# design.net
KiCad netlist of a schematic drawn in Altium Designer
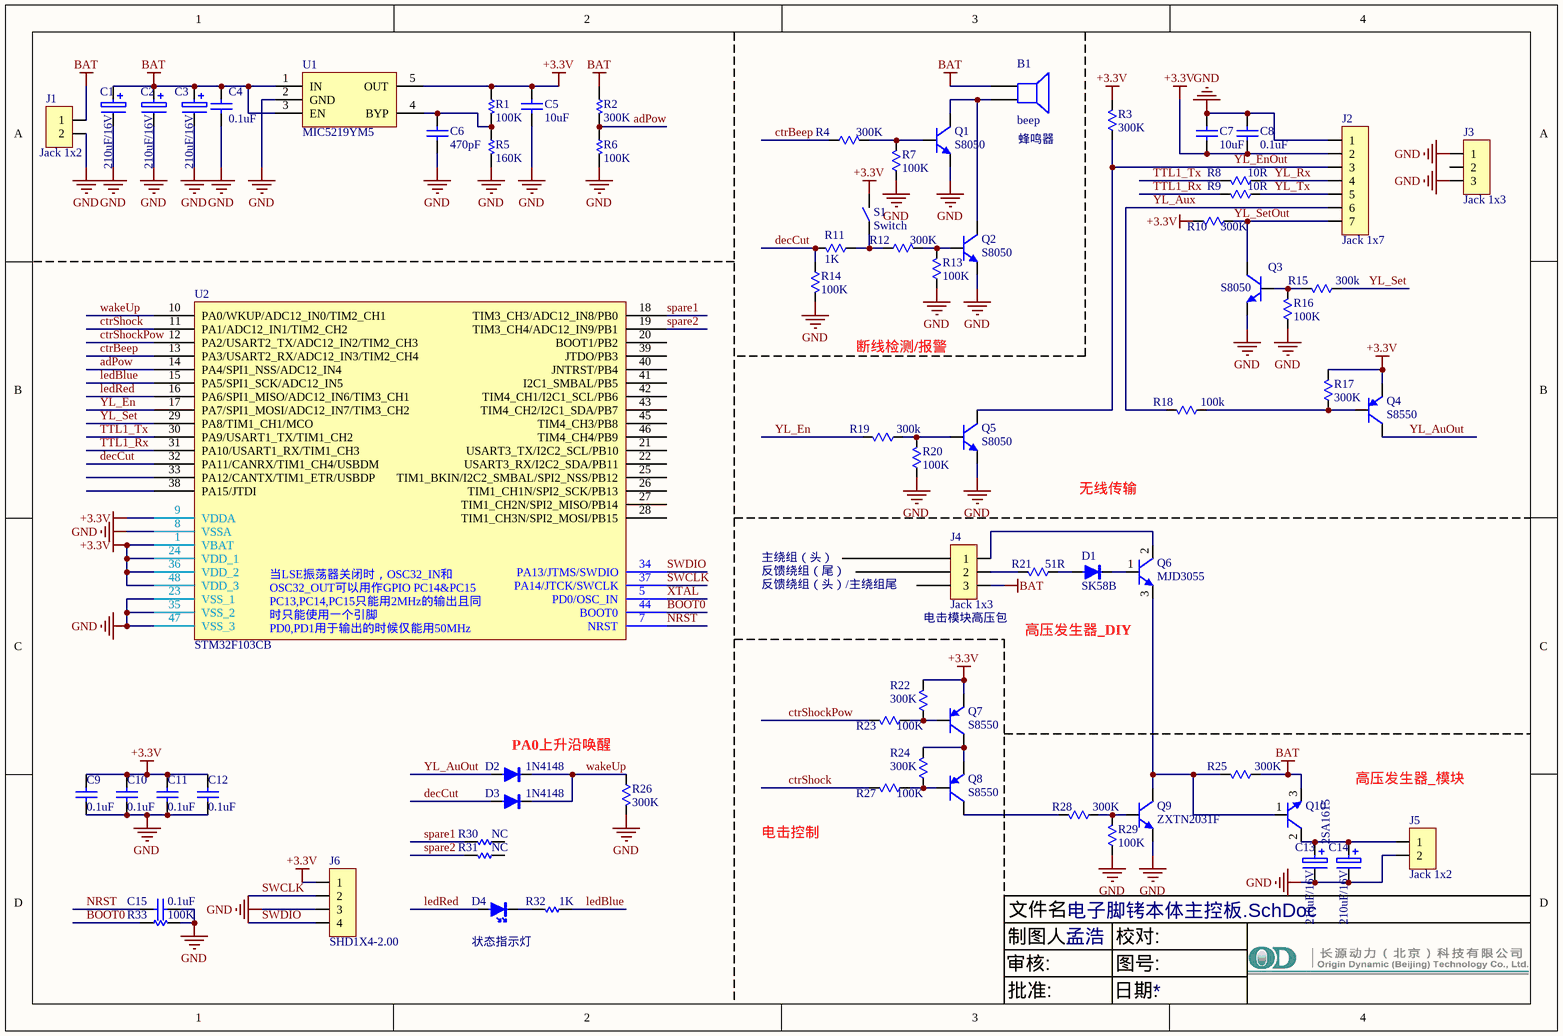
[diagram p0: 电子脚铐本体主控板.SchDoc]

(export (version "E")
  (design (tool "Eeschema 10.0.6"))
  (components
    (comp (ref "B1")
      (value "beep")
      (footprint "Jk1*2-2.0")
      (description "Loudspeaker")
      (fields (field (name "PUBLISHER") "Altium Limited"))
      (libsource (lib "Miscellaneous Devices") (part "Speaker"))
    )
    (comp (ref "C1") (value "210uF/16V") (footprint "C7343") (libsource (lib "RLCYDF") (part "Cap Poll")))
    (comp (ref "C2") (value "210uF/16V") (footprint "C7343") (libsource (lib "RLCYDF") (part "Cap Poll")))
    (comp (ref "C3") (value "210uF/16V") (footprint "C7343") (libsource (lib "RLCYDF") (part "Cap Poll")))
    (comp (ref "C4") (value "0.1uF") (footprint "C0603") (libsource (lib "RLCYDF") (part "Cap Semi")))
    (comp (ref "C5")
      (value "10uF")
      (footprint "C0603")
      (description "CAP")
      (fields (field (name "PUBLISHER") "Altium Limited"))
      (libsource (lib "Passive Components Class") (part "CAP"))
    )
    (comp (ref "C6")
      (value "470pF")
      (footprint "C0603")
      (description "CAP")
      (fields (field (name "PUBLISHER") "Altium Limited"))
      (libsource (lib "Passive Components Class") (part "CAP"))
    )
    (comp (ref "C7")
      (value "10uF")
      (footprint "C0603")
      (description "CAP")
      (fields (field (name "PUBLISHER") "Altium Limited"))
      (libsource (lib "Passive Components Class") (part "CAP"))
    )
    (comp (ref "C8")
      (value "0.1uF")
      (footprint "C0603")
      (description "CAP")
      (fields (field (name "PUBLISHER") "Altium Limited"))
      (libsource (lib "Passive Components Class") (part "CAP"))
    )
    (comp (ref "C9") (value "0.1uF") (footprint "C0603") (libsource (lib "RLCYDF") (part "Cap Semi")))
    (comp (ref "C10") (value "0.1uF") (footprint "C0603") (libsource (lib "RLCYDF") (part "Cap Semi")))
    (comp (ref "C11") (value "0.1uF") (footprint "C0603") (libsource (lib "RLCYDF") (part "Cap Semi")))
    (comp (ref "C12") (value "0.1uF") (footprint "C0603") (libsource (lib "RLCYDF") (part "Cap Semi")))
    (comp (ref "C13") (value "210uF/16V") (footprint "C7343") (libsource (lib "RLCYDF") (part "Cap Poll")))
    (comp (ref "C14") (value "210uF/16V") (footprint "C7343") (libsource (lib "RLCYDF") (part "Cap Poll")))
    (comp (ref "C15") (value "0.1uF") (footprint "C0603") (libsource (lib "RLCYDF") (part "Cap Semi")))
    (comp (ref "D1")
      (value "SK58B")
      (footprint "SMB")
      (description "Silicon Epitaxial Planar Diodes")
      (libsource (lib "Passive Components Class") (part "DIODE-SWITCHING"))
    )
    (comp (ref "D2")
      (value "1N4148")
      (footprint "SOD-80-S")
      (description "Silicon Epitaxial Planar Diodes")
      (libsource (lib "Passive Components Class") (part "DIODE-SWITCHING"))
    )
    (comp (ref "D3")
      (value "1N4148")
      (footprint "SOD-80-S")
      (description "Silicon Epitaxial Planar Diodes")
      (libsource (lib "Passive Components Class") (part "DIODE-SWITCHING"))
    )
    (comp (ref "D4")
      (value "LED")
      (footprint "Jk1*2-2.0")
      (libsource (lib "Passive Components Class") (part "LED"))
    )
    (comp (ref "J1")
      (value "Jack 1x2")
      (footprint "HDR1X2")
      (description "插座")
      (libsource (lib "Connector") (part "Jack 1x2"))
    )
    (comp (ref "J2")
      (value "Jack 1x7")
      (footprint "Jk1*7-2.0")
      (description "插座")
      (libsource (lib "Connector") (part "Jack 1x7"))
    )
    (comp (ref "J3")
      (value "Jack 1x3")
      (footprint "Jk1*3-2.0")
      (description "插座")
      (libsource (lib "Connector") (part "Jack 1x3"))
    )
    (comp (ref "J4")
      (value "Jack 1x3")
      (footprint "Jk1*3-2.0")
      (description "插座")
      (libsource (lib "") (part "Jack 1x3_1"))
    )
    (comp (ref "J5")
      (value "Jack 1x2")
      (footprint "Jk1*2-2.0")
      (description "插座")
      (libsource (lib "") (part "Jack 1x2_1"))
    )
    (comp (ref "J6")
      (value "SHD1X4-2.00")
      (footprint "Jk1*4-2.0")
      (libsource (lib "Connector Class") (part "HEADER1X4"))
    )
    (comp (ref "Q1")
      (value "S8050")
      (footprint "SOT-23")
      (description "NPN triode, 0.5A Max")
      (libsource (lib "RLCYDF") (part "S8050"))
    )
    (comp (ref "Q2")
      (value "S8050")
      (footprint "SOT-23")
      (description "NPN triode, 0.5A Max")
      (libsource (lib "RLCYDF") (part "S8050"))
    )
    (comp (ref "Q3")
      (value "S8050")
      (footprint "SOT-23")
      (description "NPN triode, 0.5A Max")
      (libsource (lib "RLCYDF") (part "S8050"))
    )
    (comp (ref "Q4")
      (value "S8550")
      (footprint "SOT-23")
      (description "PNP triode")
      (libsource (lib "RLCYDF") (part "S8550"))
    )
    (comp (ref "Q5")
      (value "S8050")
      (footprint "SOT-23")
      (description "NPN triode, 0.5A Max")
      (libsource (lib "RLCYDF") (part "S8050"))
    )
    (comp (ref "Q6") (value "MJD3055") (footprint "TO-252") (libsource (lib "ArmArmor") (part "MJD122")))
    (comp (ref "Q7")
      (value "S8550")
      (footprint "SOT-23")
      (description "PNP triode")
      (libsource (lib "RLCYDF") (part "S8550"))
    )
    (comp (ref "Q8")
      (value "S8550")
      (footprint "SOT-23")
      (description "PNP triode")
      (libsource (lib "RLCYDF") (part "S8550"))
    )
    (comp (ref "Q9")
      (value "ZXTN2031F")
      (footprint "SOT-23")
      (description "NPN triode, 0.5A Max")
      (libsource (lib "RLCYDF") (part "S8050"))
    )
    (comp (ref "Q10") (value "2SA1615") (footprint "TO-252") (libsource (lib "ArmArmor") (part "MJD122")))
    (comp (ref "R1") (value "100K") (footprint "R0603") (libsource (lib "RLCYDF") (part "Res")))
    (comp (ref "R2") (value "300K") (footprint "R0603") (libsource (lib "RLCYDF") (part "Res")))
    (comp (ref "R3")
      (value "300K")
      (footprint "R0603")
      (description "Resistor")
      (fields (field (name "PUBLISHER") "Altium Limited"))
      (libsource (lib "Passive Components Class") (part "RES"))
    )
    (comp (ref "R4")
      (value "300K")
      (footprint "R0603")
      (description "Resistor")
      (fields (field (name "PUBLISHER") "Altium Limited"))
      (libsource (lib "Passive Components Class") (part "RES"))
    )
    (comp (ref "R5") (value "160K") (footprint "R0603") (libsource (lib "RLCYDF") (part "Res")))
    (comp (ref "R6") (value "100K") (footprint "R0603") (libsource (lib "RLCYDF") (part "Res")))
    (comp (ref "R7")
      (value "100K")
      (footprint "R0603")
      (description "Resistor")
      (fields (field (name "PUBLISHER") "Altium Limited"))
      (libsource (lib "Passive Components Class") (part "RES"))
    )
    (comp (ref "R8")
      (value "10R")
      (footprint "R0603")
      (description "Resistor")
      (fields (field (name "PUBLISHER") "Altium Limited"))
      (libsource (lib "Passive Components Class") (part "RES"))
    )
    (comp (ref "R9")
      (value "10R")
      (footprint "R0603")
      (description "Resistor")
      (fields (field (name "PUBLISHER") "Altium Limited"))
      (libsource (lib "Passive Components Class") (part "RES"))
    )
    (comp (ref "R10")
      (value "300K")
      (footprint "R0603")
      (description "Resistor")
      (fields (field (name "PUBLISHER") "Altium Limited"))
      (libsource (lib "Passive Components Class") (part "RES"))
    )
    (comp (ref "R11")
      (value "1K")
      (footprint "R0603")
      (description "Resistor")
      (fields (field (name "PUBLISHER") "Altium Limited"))
      (libsource (lib "Passive Components Class") (part "RES"))
    )
    (comp (ref "R12")
      (value "300K")
      (footprint "R0603")
      (description "Resistor")
      (fields (field (name "PUBLISHER") "Altium Limited"))
      (libsource (lib "Passive Components Class") (part "RES"))
    )
    (comp (ref "R13")
      (value "100K")
      (footprint "R0603")
      (description "Resistor")
      (fields (field (name "PUBLISHER") "Altium Limited"))
      (libsource (lib "Passive Components Class") (part "RES"))
    )
    (comp (ref "R14")
      (value "100K")
      (footprint "R0603")
      (description "Resistor")
      (fields (field (name "PUBLISHER") "Altium Limited"))
      (libsource (lib "Passive Components Class") (part "RES"))
    )
    (comp (ref "R15")
      (value "300k")
      (footprint "R0603")
      (description "Resistor")
      (fields (field (name "PUBLISHER") "Altium Limited"))
      (libsource (lib "Passive Components Class") (part "RES"))
    )
    (comp (ref "R16")
      (value "100K")
      (footprint "R0603")
      (description "Resistor")
      (fields (field (name "PUBLISHER") "Altium Limited"))
      (libsource (lib "Passive Components Class") (part "RES"))
    )
    (comp (ref "R17")
      (value "300K")
      (footprint "R0603")
      (description "Resistor")
      (fields (field (name "PUBLISHER") "Altium Limited"))
      (libsource (lib "Passive Components Class") (part "RES"))
    )
    (comp (ref "R18")
      (value "100k")
      (footprint "R0603")
      (description "Resistor")
      (fields (field (name "PUBLISHER") "Altium Limited"))
      (libsource (lib "Passive Components Class") (part "RES"))
    )
    (comp (ref "R19")
      (value "300k")
      (footprint "R0603")
      (description "Resistor")
      (fields (field (name "PUBLISHER") "Altium Limited"))
      (libsource (lib "Passive Components Class") (part "RES"))
    )
    (comp (ref "R20")
      (value "100K")
      (footprint "R0603")
      (description "Resistor")
      (fields (field (name "PUBLISHER") "Altium Limited"))
      (libsource (lib "Passive Components Class") (part "RES"))
    )
    (comp (ref "R21")
      (value "51R")
      (footprint "R2512")
      (description "Resistor")
      (fields (field (name "PUBLISHER") "Altium Limited"))
      (libsource (lib "Passive Components Class") (part "RES"))
    )
    (comp (ref "R22")
      (value "300K")
      (footprint "R0603")
      (description "Resistor")
      (fields (field (name "PUBLISHER") "Altium Limited"))
      (libsource (lib "Passive Components Class") (part "RES"))
    )
    (comp (ref "R23")
      (value "100K")
      (footprint "R0603")
      (description "Resistor")
      (fields (field (name "PUBLISHER") "Altium Limited"))
      (libsource (lib "Passive Components Class") (part "RES"))
    )
    (comp (ref "R24")
      (value "300K")
      (footprint "R0603")
      (description "Resistor")
      (fields (field (name "PUBLISHER") "Altium Limited"))
      (libsource (lib "Passive Components Class") (part "RES"))
    )
    (comp (ref "R25")
      (value "300K")
      (footprint "R0603")
      (description "Resistor")
      (fields (field (name "PUBLISHER") "Altium Limited"))
      (libsource (lib "Passive Components Class") (part "RES"))
    )
    (comp (ref "R26")
      (value "300K")
      (footprint "R0603")
      (description "Resistor")
      (fields (field (name "PUBLISHER") "Altium Limited"))
      (libsource (lib "Passive Components Class") (part "RES"))
    )
    (comp (ref "R27")
      (value "100K")
      (footprint "R0603")
      (description "Resistor")
      (fields (field (name "PUBLISHER") "Altium Limited"))
      (libsource (lib "Passive Components Class") (part "RES"))
    )
    (comp (ref "R28")
      (value "300K")
      (footprint "R0603")
      (description "Resistor")
      (fields (field (name "PUBLISHER") "Altium Limited"))
      (libsource (lib "Passive Components Class") (part "RES"))
    )
    (comp (ref "R29")
      (value "100K")
      (footprint "R0603")
      (description "Resistor")
      (fields (field (name "PUBLISHER") "Altium Limited"))
      (libsource (lib "Passive Components Class") (part "RES"))
    )
    (comp (ref "R30") (value "NC") (footprint "R0603") (libsource (lib "RLCYDF") (part "Res")))
    (comp (ref "R31") (value "NC") (footprint "R0603") (libsource (lib "RLCYDF") (part "Res")))
    (comp (ref "R32") (value "1K") (footprint "R0603") (libsource (lib "RLCYDF") (part "Res")))
    (comp (ref "R33") (value "100K") (footprint "R0603") (libsource (lib "RLCYDF") (part "Res")))
    (comp (ref "S1") (value "Switch") (footprint "Jk1*2-2.0") (libsource (lib "Connector") (part "Sw")))
    (comp (ref "U1") (value "MIC5219YM5") (footprint "SOT-23-5") (libsource (lib "Power") (part "MIC5205")))
    (comp (ref "U2")
      (value "STM32F103CB")
      (footprint "LQFP48")
      (libsource (lib "stm32") (part "STM32F103Cx"))
    )
  )
  (nets
    (net (code "1") (name "+3.3V") (class "Default")
      (node (ref "C10") (pin "1") (pinfunction "1_1") (pintype "passive"))
      (node (ref "C11") (pin "1") (pinfunction "1_1") (pintype "passive"))
      (node (ref "C12") (pin "1") (pinfunction "1_1") (pintype "passive"))
      (node (ref "C5") (pin "1") (pinfunction "1_1") (pintype "passive"))
      (node (ref "C7") (pin "1") (pinfunction "1_1") (pintype "passive"))
      (node (ref "C8") (pin "1") (pinfunction "1_1") (pintype "passive"))
      (node (ref "C9") (pin "1") (pinfunction "1_1") (pintype "passive"))
      (node (ref "J2") (pin "2") (pinfunction "2_2") (pintype "passive"))
      (node (ref "J6") (pin "1") (pinfunction "1_1") (pintype "passive"))
      (node (ref "Q4") (pin "2") (pinfunction "e_2") (pintype "passive"))
      (node (ref "Q7") (pin "2") (pinfunction "e_2") (pintype "passive"))
      (node (ref "R1") (pin "1") (pinfunction "1_1") (pintype "passive"))
      (node (ref "R10") (pin "2") (pinfunction "2_2") (pintype "passive"))
      (node (ref "R17") (pin "2") (pinfunction "2_2") (pintype "passive"))
      (node (ref "R22") (pin "2") (pinfunction "2_2") (pintype "passive"))
      (node (ref "R3") (pin "2") (pinfunction "2_2") (pintype "passive"))
      (node (ref "S1") (pin "2") (pinfunction "2_2") (pintype "passive"))
      (node (ref "U1") (pin "5") (pinfunction "OUT_5") (pintype "passive"))
      (node (ref "U2") (pin "1") (pinfunction "VBAT_1") (pintype "power_in"))
      (node (ref "U2") (pin "24") (pinfunction "VDD_1_24") (pintype "power_in"))
      (node (ref "U2") (pin "36") (pinfunction "VDD_2_36") (pintype "power_in"))
      (node (ref "U2") (pin "48") (pinfunction "VDD_3_48") (pintype "power_in"))
      (node (ref "U2") (pin "9") (pinfunction "VDDA_9") (pintype "power_in"))
    )
    (net (code "2") (name "/BOOT0") (class "Default")
      (node (ref "R33") (pin "1") (pinfunction "1_1") (pintype "passive"))
      (node (ref "U2") (pin "44") (pinfunction "BOOT0_44") (pintype "passive"))
    )
    (net (code "3") (name "/NRST") (class "Default")
      (node (ref "C15") (pin "1") (pinfunction "1_1") (pintype "passive"))
      (node (ref "U2") (pin "7") (pinfunction "NRST_7") (pintype "passive"))
    )
    (net (code "4") (name "/SWCLK") (class "Default")
      (node (ref "J6") (pin "2") (pinfunction "2_2") (pintype "passive"))
      (node (ref "U2") (pin "37") (pinfunction "PA14/JTCK/SWCLK_37") (pintype "passive"))
    )
    (net (code "5") (name "/SWDIO") (class "Default")
      (node (ref "J6") (pin "4") (pinfunction "4_4") (pintype "passive"))
      (node (ref "U2") (pin "34") (pinfunction "PA13/JTMS/SWDIO_34") (pintype "passive"))
    )
    (net (code "6") (name "/TTL1_Rx") (class "Default")
      (node (ref "R9") (pin "2") (pinfunction "2_2") (pintype "passive"))
      (node (ref "U2") (pin "31") (pinfunction "PA10/USART1_RX/TIM1_CH3_31") (pintype "passive"))
    )
    (net (code "7") (name "/TTL1_Tx") (class "Default")
      (node (ref "R8") (pin "2") (pinfunction "2_2") (pintype "passive"))
      (node (ref "U2") (pin "30") (pinfunction "PA9/USART1_TX/TIM1_CH2_30") (pintype "passive"))
    )
    (net (code "8") (name "/XTAL") (class "Default")
      (node (ref "U2") (pin "5") (pinfunction "PD0/OSC_IN_5") (pintype "passive"))
    )
    (net (code "9") (name "/YL_AuOut") (class "Default")
      (node (ref "D2") (pin "1") (pinfunction "A_1") (pintype "passive"))
      (node (ref "Q4") (pin "3") (pinfunction "c_3") (pintype "passive"))
    )
    (net (code "10") (name "/YL_Aux") (class "Default")
      (node (ref "J2") (pin "6") (pinfunction "6_6") (pintype "passive"))
      (node (ref "R18") (pin "2") (pinfunction "2_2") (pintype "passive"))
    )
    (net (code "11") (name "/YL_En") (class "Default")
      (node (ref "R19") (pin "2") (pinfunction "2_2") (pintype "passive"))
      (node (ref "U2") (pin "17") (pinfunction "PA7/SPI1_MOSI/ADC12_IN7/TIM3_CH2_17") (pintype "passive"))
    )
    (net (code "12") (name "/YL_EnOut") (class "Default")
      (node (ref "J2") (pin "3") (pinfunction "3_3") (pintype "passive"))
      (node (ref "Q5") (pin "3") (pinfunction "c_3") (pintype "passive"))
      (node (ref "R3") (pin "1") (pinfunction "1_1") (pintype "passive"))
    )
    (net (code "13") (name "/YL_Rx") (class "Default")
      (node (ref "J2") (pin "4") (pinfunction "4_4") (pintype "passive"))
      (node (ref "R8") (pin "1") (pinfunction "1_1") (pintype "passive"))
    )
    (net (code "14") (name "/YL_Set") (class "Default")
      (node (ref "R15") (pin "1") (pinfunction "1_1") (pintype "passive"))
      (node (ref "U2") (pin "29") (pinfunction "PA8/TIM1_CH1/MCO_29") (pintype "passive"))
    )
    (net (code "15") (name "/YL_SetOut") (class "Default")
      (node (ref "J2") (pin "7") (pinfunction "7_7") (pintype "passive"))
      (node (ref "Q3") (pin "3") (pinfunction "c_3") (pintype "passive"))
      (node (ref "R10") (pin "1") (pinfunction "1_1") (pintype "passive"))
    )
    (net (code "16") (name "/YL_Tx") (class "Default")
      (node (ref "J2") (pin "5") (pinfunction "5_5") (pintype "passive"))
      (node (ref "R9") (pin "1") (pinfunction "1_1") (pintype "passive"))
    )
    (net (code "17") (name "/adPow") (class "Default")
      (node (ref "R2") (pin "2") (pinfunction "2_2") (pintype "passive"))
      (node (ref "R6") (pin "1") (pinfunction "1_1") (pintype "passive"))
      (node (ref "U2") (pin "14") (pinfunction "PA4/SPI1_NSS/ADC12_IN4_14") (pintype "passive"))
    )
    (net (code "18") (name "/ctrBeep") (class "Default")
      (node (ref "R4") (pin "1") (pinfunction "1_1") (pintype "passive"))
      (node (ref "U2") (pin "13") (pinfunction "PA3/USART2_RX/ADC12_IN3/TIM2_CH4_13") (pintype "passive"))
    )
    (net (code "19") (name "/ctrShock") (class "Default")
      (node (ref "R27") (pin "2") (pinfunction "2_2") (pintype "passive"))
      (node (ref "U2") (pin "11") (pinfunction "PA1/ADC12_IN1/TIM2_CH2_11") (pintype "passive"))
    )
    (net (code "20") (name "/ctrShockPow") (class "Default")
      (node (ref "R23") (pin "2") (pinfunction "2_2") (pintype "passive"))
      (node (ref "U2") (pin "12") (pinfunction "PA2/USART2_TX/ADC12_IN2/TIM2_CH3_12") (pintype "passive"))
    )
    (net (code "21") (name "/decCut") (class "Default")
      (node (ref "D3") (pin "1") (pinfunction "A_1") (pintype "passive"))
      (node (ref "R11") (pin "2") (pinfunction "2_2") (pintype "passive"))
      (node (ref "R14") (pin "1") (pinfunction "1_1") (pintype "passive"))
      (node (ref "U2") (pin "32") (pinfunction "PA11/CANRX/TIM1_CH4/USBDM_32") (pintype "passive"))
    )
    (net (code "22") (name "/ledBlue") (class "Default")
      (node (ref "R32") (pin "1") (pinfunction "1_1") (pintype "passive"))
      (node (ref "U2") (pin "15") (pinfunction "PA5/SPI1_SCK/ADC12_IN5_15") (pintype "passive"))
    )
    (net (code "23") (name "/ledRed") (class "Default")
      (node (ref "D4") (pin "1") (pinfunction "A_1") (pintype "passive"))
      (node (ref "U2") (pin "16") (pinfunction "PA6/SPI1_MISO/ADC12_IN6/TIM3_CH1_16") (pintype "passive"))
    )
    (net (code "24") (name "/spare1") (class "Default")
      (node (ref "R30") (pin "2") (pinfunction "2_2") (pintype "passive"))
      (node (ref "U2") (pin "18") (pinfunction "TIM3_CH3/ADC12_IN8/PB0_18") (pintype "passive"))
    )
    (net (code "25") (name "/spare2") (class "Default")
      (node (ref "R31") (pin "2") (pinfunction "2_2") (pintype "passive"))
      (node (ref "U2") (pin "19") (pinfunction "TIM3_CH4/ADC12_IN9/PB1_19") (pintype "passive"))
    )
    (net (code "26") (name "/wakeUp") (class "Default")
      (node (ref "D2") (pin "2") (pinfunction "K_2") (pintype "passive"))
      (node (ref "D3") (pin "2") (pinfunction "K_2") (pintype "passive"))
      (node (ref "R26") (pin "1") (pinfunction "1_1") (pintype "passive"))
      (node (ref "U2") (pin "10") (pinfunction "PA0/WKUP/ADC12_IN0/TIM2_CH1_10") (pintype "passive"))
    )
    (net (code "27") (name "BAT") (class "Default")
      (node (ref "B1") (pin "1") (pinfunction "1_1") (pintype "passive"))
      (node (ref "C1") (pin "1") (pinfunction "1_1") (pintype "passive"))
      (node (ref "C2") (pin "1") (pinfunction "1_1") (pintype "passive"))
      (node (ref "C3") (pin "1") (pinfunction "1_1") (pintype "passive"))
      (node (ref "C4") (pin "2") (pinfunction "2_2") (pintype "passive"))
      (node (ref "J1") (pin "1") (pinfunction "1_1") (pintype "passive"))
      (node (ref "J4") (pin "3") (pinfunction "3_3") (pintype "passive"))
      (node (ref "Q10") (pin "3") (pinfunction "E_3") (pintype "passive"))
      (node (ref "R2") (pin "1") (pinfunction "1_1") (pintype "passive"))
      (node (ref "R25") (pin "1") (pinfunction "1_1") (pintype "passive"))
      (node (ref "U1") (pin "1") (pinfunction "IN_1") (pintype "passive"))
      (node (ref "U1") (pin "3") (pinfunction "EN_3") (pintype "passive"))
    )
    (net (code "28") (name "GND") (class "Default")
      (node (ref "C1") (pin "2") (pinfunction "2_2") (pintype "passive"))
      (node (ref "C10") (pin "2") (pinfunction "2_2") (pintype "passive"))
      (node (ref "C11") (pin "2") (pinfunction "2_2") (pintype "passive"))
      (node (ref "C12") (pin "2") (pinfunction "2_2") (pintype "passive"))
      (node (ref "C13") (pin "2") (pinfunction "2_2") (pintype "passive"))
      (node (ref "C14") (pin "2") (pinfunction "2_2") (pintype "passive"))
      (node (ref "C15") (pin "2") (pinfunction "2_2") (pintype "passive"))
      (node (ref "C2") (pin "2") (pinfunction "2_2") (pintype "passive"))
      (node (ref "C3") (pin "2") (pinfunction "2_2") (pintype "passive"))
      (node (ref "C4") (pin "1") (pinfunction "1_1") (pintype "passive"))
      (node (ref "C5") (pin "2") (pinfunction "2_2") (pintype "passive"))
      (node (ref "C6") (pin "2") (pinfunction "2_2") (pintype "passive"))
      (node (ref "C7") (pin "2") (pinfunction "2_2") (pintype "passive"))
      (node (ref "C8") (pin "2") (pinfunction "2_2") (pintype "passive"))
      (node (ref "C9") (pin "2") (pinfunction "2_2") (pintype "passive"))
      (node (ref "J1") (pin "2") (pinfunction "2_2") (pintype "passive"))
      (node (ref "J2") (pin "1") (pinfunction "1_1") (pintype "passive"))
      (node (ref "J3") (pin "1") (pinfunction "1_1") (pintype "passive"))
      (node (ref "J3") (pin "3") (pinfunction "3_3") (pintype "passive"))
      (node (ref "J5") (pin "2") (pinfunction "2_2") (pintype "passive"))
      (node (ref "J6") (pin "3") (pinfunction "3_3") (pintype "passive"))
      (node (ref "Q1") (pin "2") (pinfunction "e_2") (pintype "passive"))
      (node (ref "Q2") (pin "2") (pinfunction "e_2") (pintype "passive"))
      (node (ref "Q3") (pin "2") (pinfunction "e_2") (pintype "passive"))
      (node (ref "Q5") (pin "2") (pinfunction "e_2") (pintype "passive"))
      (node (ref "Q9") (pin "2") (pinfunction "e_2") (pintype "passive"))
      (node (ref "R13") (pin "1") (pinfunction "1_1") (pintype "passive"))
      (node (ref "R14") (pin "2") (pinfunction "2_2") (pintype "passive"))
      (node (ref "R16") (pin "1") (pinfunction "1_1") (pintype "passive"))
      (node (ref "R20") (pin "1") (pinfunction "1_1") (pintype "passive"))
      (node (ref "R26") (pin "2") (pinfunction "2_2") (pintype "passive"))
      (node (ref "R29") (pin "1") (pinfunction "1_1") (pintype "passive"))
      (node (ref "R33") (pin "2") (pinfunction "2_2") (pintype "passive"))
      (node (ref "R5") (pin "2") (pinfunction "2_2") (pintype "passive"))
      (node (ref "R6") (pin "2") (pinfunction "2_2") (pintype "passive"))
      (node (ref "R7") (pin "1") (pinfunction "1_1") (pintype "passive"))
      (node (ref "U1") (pin "2") (pinfunction "GND_2") (pintype "passive"))
      (node (ref "U2") (pin "23") (pinfunction "VSS_1_23") (pintype "power_in"))
      (node (ref "U2") (pin "35") (pinfunction "VSS_2_35") (pintype "power_in"))
      (node (ref "U2") (pin "47") (pinfunction "VSS_3_47") (pintype "power_in"))
      (node (ref "U2") (pin "8") (pinfunction "VSSA_8") (pintype "power_in"))
    )
    (net (code "29") (name "Net-(D1-A)") (class "Default")
      (node (ref "D1") (pin "1") (pinfunction "A_1") (pintype "passive"))
      (node (ref "R21") (pin "1") (pinfunction "1_1") (pintype "passive"))
    )
    (net (code "30") (name "Net-(D1-K)") (class "Default")
      (node (ref "D1") (pin "2") (pinfunction "K_2") (pintype "passive"))
      (node (ref "Q6") (pin "1") (pinfunction "B_1") (pintype "passive"))
    )
    (net (code "31") (name "Net-(D4-K)") (class "Default")
      (node (ref "D4") (pin "2") (pinfunction "K_2") (pintype "passive"))
      (node (ref "R32") (pin "2") (pinfunction "2_2") (pintype "passive"))
    )
    (net (code "32") (name "Net-(J4-Pad2)") (class "Default")
      (node (ref "J4") (pin "2") (pinfunction "2_2") (pintype "passive"))
      (node (ref "R21") (pin "2") (pinfunction "2_2") (pintype "passive"))
    )
    (net (code "33") (name "Net-(Q1-b)") (class "Default")
      (node (ref "Q1") (pin "1") (pinfunction "b_1") (pintype "passive"))
      (node (ref "R4") (pin "2") (pinfunction "2_2") (pintype "passive"))
      (node (ref "R7") (pin "2") (pinfunction "2_2") (pintype "passive"))
    )
    (net (code "34") (name "Net-(Q1-c)") (class "Default")
      (node (ref "B1") (pin "2") (pinfunction "2_2") (pintype "passive"))
      (node (ref "Q1") (pin "3") (pinfunction "c_3") (pintype "passive"))
      (node (ref "Q2") (pin "3") (pinfunction "c_3") (pintype "passive"))
    )
    (net (code "35") (name "Net-(Q2-b)") (class "Default")
      (node (ref "Q2") (pin "1") (pinfunction "b_1") (pintype "passive"))
      (node (ref "R12") (pin "2") (pinfunction "2_2") (pintype "passive"))
      (node (ref "R13") (pin "2") (pinfunction "2_2") (pintype "passive"))
    )
    (net (code "36") (name "Net-(Q3-b)") (class "Default")
      (node (ref "Q3") (pin "1") (pinfunction "b_1") (pintype "passive"))
      (node (ref "R15") (pin "2") (pinfunction "2_2") (pintype "passive"))
      (node (ref "R16") (pin "2") (pinfunction "2_2") (pintype "passive"))
    )
    (net (code "37") (name "Net-(Q4-b)") (class "Default")
      (node (ref "Q4") (pin "1") (pinfunction "b_1") (pintype "passive"))
      (node (ref "R17") (pin "1") (pinfunction "1_1") (pintype "passive"))
      (node (ref "R18") (pin "1") (pinfunction "1_1") (pintype "passive"))
    )
    (net (code "38") (name "Net-(Q5-b)") (class "Default")
      (node (ref "Q5") (pin "1") (pinfunction "b_1") (pintype "passive"))
      (node (ref "R19") (pin "1") (pinfunction "1_1") (pintype "passive"))
      (node (ref "R20") (pin "2") (pinfunction "2_2") (pintype "passive"))
    )
    (net (code "39") (name "Net-(Q6-C)") (class "Default")
      (node (ref "J4") (pin "1") (pinfunction "1_1") (pintype "passive"))
      (node (ref "Q6") (pin "2") (pinfunction "C_2") (pintype "passive"))
    )
    (net (code "40") (name "Net-(Q7-b)") (class "Default")
      (node (ref "Q7") (pin "1") (pinfunction "b_1") (pintype "passive"))
      (node (ref "R22") (pin "1") (pinfunction "1_1") (pintype "passive"))
      (node (ref "R23") (pin "1") (pinfunction "1_1") (pintype "passive"))
    )
    (net (code "41") (name "Net-(Q7-c)") (class "Default")
      (node (ref "Q7") (pin "3") (pinfunction "c_3") (pintype "passive"))
      (node (ref "Q8") (pin "2") (pinfunction "e_2") (pintype "passive"))
      (node (ref "R24") (pin "2") (pinfunction "2_2") (pintype "passive"))
    )
    (net (code "42") (name "Net-(Q8-b)") (class "Default")
      (node (ref "Q8") (pin "1") (pinfunction "b_1") (pintype "passive"))
      (node (ref "R24") (pin "1") (pinfunction "1_1") (pintype "passive"))
      (node (ref "R27") (pin "1") (pinfunction "1_1") (pintype "passive"))
    )
    (net (code "43") (name "Net-(Q8-c)") (class "Default")
      (node (ref "Q8") (pin "3") (pinfunction "c_3") (pintype "passive"))
      (node (ref "R28") (pin "2") (pinfunction "2_2") (pintype "passive"))
    )
    (net (code "44") (name "Net-(Q9-b)") (class "Default")
      (node (ref "Q9") (pin "1") (pinfunction "b_1") (pintype "passive"))
      (node (ref "R28") (pin "1") (pinfunction "1_1") (pintype "passive"))
      (node (ref "R29") (pin "2") (pinfunction "2_2") (pintype "passive"))
    )
    (net (code "45") (name "Net-(Q10-B)") (class "Default")
      (node (ref "Q10") (pin "1") (pinfunction "B_1") (pintype "passive"))
      (node (ref "Q6") (pin "3") (pinfunction "E_3") (pintype "passive"))
      (node (ref "Q9") (pin "3") (pinfunction "c_3") (pintype "passive"))
      (node (ref "R25") (pin "2") (pinfunction "2_2") (pintype "passive"))
    )
    (net (code "46") (name "Net-(Q10-C)") (class "Default")
      (node (ref "C13") (pin "1") (pinfunction "1_1") (pintype "passive"))
      (node (ref "C14") (pin "1") (pinfunction "1_1") (pintype "passive"))
      (node (ref "J5") (pin "1") (pinfunction "1_1") (pintype "passive"))
      (node (ref "Q10") (pin "2") (pinfunction "C_2") (pintype "passive"))
    )
    (net (code "47") (name "Net-(R11-Pad1)") (class "Default")
      (node (ref "R11") (pin "1") (pinfunction "1_1") (pintype "passive"))
      (node (ref "R12") (pin "1") (pinfunction "1_1") (pintype "passive"))
      (node (ref "S1") (pin "1") (pinfunction "1_1") (pintype "passive"))
    )
    (net (code "48") (name "Net-(U1-BYP)") (class "Default")
      (node (ref "C6") (pin "1") (pinfunction "1_1") (pintype "passive"))
      (node (ref "R1") (pin "2") (pinfunction "2_2") (pintype "passive"))
      (node (ref "R5") (pin "1") (pinfunction "1_1") (pintype "passive"))
      (node (ref "U1") (pin "4") (pinfunction "BYP_4") (pintype "passive"))
    )
    (net (code "49") (name "unconnected-(J3-Pad2)") (class "Default")
      (node (ref "J3") (pin "2") (pinfunction "2_2") (pintype "passive"))
    )
    (net (code "50") (name "unconnected-(R30-Pad1)") (class "Default")
      (node (ref "R30") (pin "1") (pinfunction "1_1") (pintype "passive"))
    )
    (net (code "51") (name "unconnected-(R31-Pad1)") (class "Default")
      (node (ref "R31") (pin "1") (pinfunction "1_1") (pintype "passive"))
    )
    (net (code "52") (name "unconnected-(U2-BOOT1{slash}PB2-Pad20)") (class "Default")
      (node (ref "U2") (pin "20") (pinfunction "BOOT1/PB2_20") (pintype "passive"))
    )
    (net (code "53") (name "unconnected-(U2-I2C1_SMBAL{slash}PB5-Pad41)") (class "Default")
      (node (ref "U2") (pin "41") (pinfunction "I2C1_SMBAL/PB5_41") (pintype "passive"))
    )
    (net (code "54") (name "unconnected-(U2-JNTRST{slash}PB4-Pad40)") (class "Default")
      (node (ref "U2") (pin "40") (pinfunction "JNTRST/PB4_40") (pintype "passive"))
    )
    (net (code "55") (name "unconnected-(U2-JTDO{slash}PB3-Pad39)") (class "Default")
      (node (ref "U2") (pin "39") (pinfunction "JTDO/PB3_39") (pintype "passive"))
    )
    (net (code "56") (name "unconnected-(U2-PA12{slash}CANTX{slash}TIM1_ETR{slash}USBDP-Pad33)") (class "Default")
      (node (ref "U2") (pin "33") (pinfunction "PA12/CANTX/TIM1_ETR/USBDP_33") (pintype "passive"))
    )
    (net (code "57") (name "unconnected-(U2-PA15{slash}JTDI-Pad38)") (class "Default")
      (node (ref "U2") (pin "38") (pinfunction "PA15/JTDI_38") (pintype "passive"))
    )
    (net (code "58") (name "unconnected-(U2-PC13-TAMPER-RTC-Pad2)") (class "Default")
      (node (ref "U2") (pin "2") (pinfunction "PC13-TAMPER-RTC_2") (pintype "passive"))
    )
    (net (code "59") (name "unconnected-(U2-PC14-OSC32_IN-Pad3)") (class "Default")
      (node (ref "U2") (pin "3") (pinfunction "PC14-OSC32_IN_3") (pintype "passive"))
    )
    (net (code "60") (name "unconnected-(U2-PC15-OSC32_OUT-Pad4)") (class "Default")
      (node (ref "U2") (pin "4") (pinfunction "PC15-OSC32_OUT_4") (pintype "passive"))
    )
    (net (code "61") (name "unconnected-(U2-PD1{slash}OSC_OUT-Pad6)") (class "Default")
      (node (ref "U2") (pin "6") (pinfunction "PD1/OSC_OUT_6") (pintype "passive"))
    )
    (net (code "62") (name "unconnected-(U2-TIM1_BKIN{slash}I2C2_SMBAL{slash}SPI2_NSS{slash}PB12-Pad25)") (class "Default")
      (node (ref "U2") (pin "25") (pinfunction "TIM1_BKIN/I2C2_SMBAL/SPI2_NSS/PB12_25") (pintype "passive"))
    )
    (net (code "63") (name "unconnected-(U2-TIM1_CH1N{slash}SPI2_SCK{slash}PB13-Pad26)") (class "Default")
      (node (ref "U2") (pin "26") (pinfunction "TIM1_CH1N/SPI2_SCK/PB13_26") (pintype "passive"))
    )
    (net (code "64") (name "unconnected-(U2-TIM1_CH2N{slash}SPI2_MISO{slash}PB14-Pad27)") (class "Default")
      (node (ref "U2") (pin "27") (pinfunction "TIM1_CH2N/SPI2_MISO/PB14_27") (pintype "passive"))
    )
    (net (code "65") (name "unconnected-(U2-TIM1_CH3N{slash}SPI2_MOSI{slash}PB15-Pad28)") (class "Default")
      (node (ref "U2") (pin "28") (pinfunction "TIM1_CH3N/SPI2_MOSI/PB15_28") (pintype "passive"))
    )
    (net (code "66") (name "unconnected-(U2-TIM4_CH1{slash}I2C1_SCL{slash}PB6-Pad42)") (class "Default")
      (node (ref "U2") (pin "42") (pinfunction "TIM4_CH1/I2C1_SCL/PB6_42") (pintype "passive"))
    )
    (net (code "67") (name "unconnected-(U2-TIM4_CH2{slash}I2C1_SDA{slash}PB7-Pad43)") (class "Default")
      (node (ref "U2") (pin "43") (pinfunction "TIM4_CH2/I2C1_SDA/PB7_43") (pintype "passive"))
    )
    (net (code "68") (name "unconnected-(U2-TIM4_CH3{slash}PB8-Pad45)") (class "Default")
      (node (ref "U2") (pin "45") (pinfunction "TIM4_CH3/PB8_45") (pintype "passive"))
    )
    (net (code "69") (name "unconnected-(U2-TIM4_CH4{slash}PB9-Pad46)") (class "Default")
      (node (ref "U2") (pin "46") (pinfunction "TIM4_CH4/PB9_46") (pintype "passive"))
    )
    (net (code "70") (name "unconnected-(U2-USART3_RX{slash}I2C2_SDA{slash}PB11-Pad22)") (class "Default")
      (node (ref "U2") (pin "22") (pinfunction "USART3_RX/I2C2_SDA/PB11_22") (pintype "passive"))
    )
    (net (code "71") (name "unconnected-(U2-USART3_TX{slash}I2C2_SCL{slash}PB10-Pad21)") (class "Default")
      (node (ref "U2") (pin "21") (pinfunction "USART3_TX/I2C2_SCL/PB10_21") (pintype "passive"))
    )
  )
)
